# output_amp.net
KiCad netlist of a schematic drawn in EAGLE
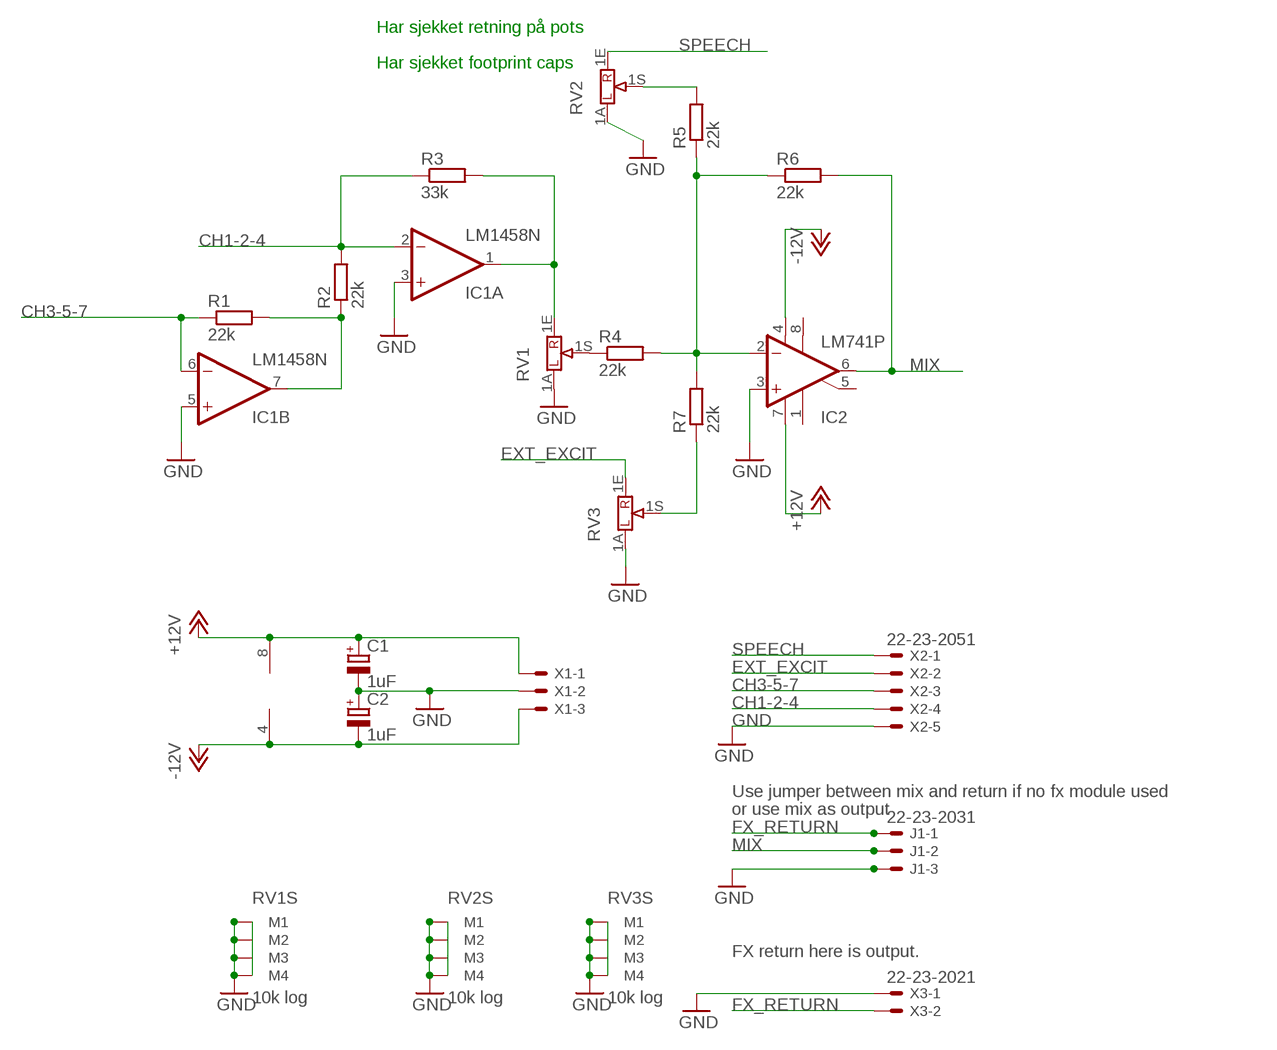
[diagram p0: schematic, sheet 1]

(export (version "E")
  (design (tool "Eeschema 10.0.6"))
  (components
    (comp (ref "C1")
      (value "1uF")
      (footprint "eagle-import:E2,5-5")
      (libsource (lib "eagle-import") (part "CPOL-EUE2.5-5"))
    )
    (comp (ref "C2")
      (value "1uF")
      (footprint "eagle-import:E2,5-5")
      (libsource (lib "eagle-import") (part "CPOL-EUE2.5-5"))
    )
    (comp (ref "IC1")
      (value "LM1458N")
      (footprint "eagle-import:DIL08")
      (libsource (lib "eagle-import") (part "1458NLM"))
    )
    (comp (ref "IC2")
      (value "LM741P")
      (footprint "eagle-import:DIL08")
      (libsource (lib "eagle-import") (part "741PLM"))
    )
    (comp (ref "J1")
      (value "22-23-2031")
      (footprint "eagle-import:22-23-2031")
      (fields (field (name "MF") "MOLEX"))
      (libsource (lib "eagle-import") (part "22-23-2031"))
    )
    (comp (ref "R1")
      (value "22k")
      (footprint "eagle-import:0207_7")
      (libsource (lib "eagle-import") (part "R-EU_0207/7"))
    )
    (comp (ref "R2")
      (value "22k")
      (footprint "eagle-import:0207_7")
      (libsource (lib "eagle-import") (part "R-EU_0207/7"))
    )
    (comp (ref "R3")
      (value "33k")
      (footprint "eagle-import:0207_7")
      (libsource (lib "eagle-import") (part "R-EU_0207/7"))
    )
    (comp (ref "R4")
      (value "22k")
      (footprint "eagle-import:0207_7")
      (libsource (lib "eagle-import") (part "R-EU_0207/7"))
    )
    (comp (ref "R5")
      (value "22k")
      (footprint "eagle-import:0207_7")
      (libsource (lib "eagle-import") (part "R-EU_0207/7"))
    )
    (comp (ref "R6")
      (value "22k")
      (footprint "eagle-import:0207_7")
      (libsource (lib "eagle-import") (part "R-EU_0207/7"))
    )
    (comp (ref "R7")
      (value "22k")
      (footprint "eagle-import:0207_7")
      (libsource (lib "eagle-import") (part "R-EU_0207/7"))
    )
    (comp (ref "RV1")
      (value "10k log")
      (footprint "eagle-import:POT16_W_BRACKET")
      (libsource (lib "eagle-import") (part "POT16_W_BRACKET{dblquote}{dblquote}"))
    )
    (comp (ref "RV2")
      (value "10k log")
      (footprint "eagle-import:POT16_W_BRACKET")
      (libsource (lib "eagle-import") (part "POT16_W_BRACKET{dblquote}{dblquote}"))
    )
    (comp (ref "RV3")
      (value "10k log")
      (footprint "eagle-import:POT16_W_BRACKET")
      (libsource (lib "eagle-import") (part "POT16_W_BRACKET{dblquote}{dblquote}"))
    )
    (comp (ref "X1")
      (value "KK-156-3")
      (footprint "eagle-import:KK-156-3")
      (libsource (lib "eagle-import") (part "KK-156-3"))
    )
    (comp (ref "X2")
      (value "22-23-2051")
      (footprint "eagle-import:22-23-2051")
      (fields (field (name "MF") "MOLEX"))
      (libsource (lib "eagle-import") (part "22-23-2051"))
    )
    (comp (ref "X3")
      (value "22-23-2021")
      (footprint "eagle-import:22-23-2021")
      (fields (field (name "MF") "MOLEX"))
      (libsource (lib "eagle-import") (part "22-23-2021"))
    )
  )
  (nets
    (net (code "1") (name "+12V") (class "Default")
      (node (ref "C1") (pin "+") (pinfunction "+_+") (pintype "passive"))
      (node (ref "IC1") (pin "8") (pinfunction "V+_8") (pintype "power_in"))
      (node (ref "IC2") (pin "7") (pinfunction "V+_7") (pintype "power_in"))
      (node (ref "X1") (pin "1") (pinfunction "S_1") (pintype "passive"))
    )
    (net (code "2") (name "-12V") (class "Default")
      (node (ref "C2") (pin "-") (pinfunction "-_-") (pintype "passive"))
      (node (ref "IC1") (pin "4") (pinfunction "V-_4") (pintype "power_in"))
      (node (ref "IC2") (pin "4") (pinfunction "V-_4") (pintype "power_in"))
      (node (ref "X1") (pin "3") (pinfunction "S_3") (pintype "passive"))
    )
    (net (code "3") (name "/CH1-2-4") (class "Default")
      (node (ref "IC1") (pin "2") (pinfunction "-IN_2") (pintype "input"))
      (node (ref "R2") (pin "2") (pinfunction "2_2") (pintype "passive"))
      (node (ref "R3") (pin "1") (pinfunction "1_1") (pintype "passive"))
      (node (ref "X2") (pin "4") (pinfunction "S_4") (pintype "passive"))
    )
    (net (code "4") (name "/CH3-5-7") (class "Default")
      (node (ref "IC1") (pin "6") (pinfunction "-IN_6") (pintype "input"))
      (node (ref "R1") (pin "1") (pinfunction "1_1") (pintype "passive"))
      (node (ref "X2") (pin "3") (pinfunction "S_3") (pintype "passive"))
    )
    (net (code "5") (name "/EXT_EXCIT") (class "Default")
      (node (ref "RV3") (pin "1E") (pinfunction "1E_1E") (pintype "passive"))
      (node (ref "X2") (pin "2") (pinfunction "S_2") (pintype "passive"))
    )
    (net (code "6") (name "/FX_RETURN") (class "Default")
      (node (ref "J1") (pin "1") (pinfunction "S_1") (pintype "passive"))
      (node (ref "X3") (pin "2") (pinfunction "S_2") (pintype "passive"))
    )
    (net (code "7") (name "/MIX") (class "Default")
      (node (ref "IC2") (pin "6") (pinfunction "OUT_6") (pintype "output"))
      (node (ref "J1") (pin "2") (pinfunction "S_2") (pintype "passive"))
      (node (ref "R6") (pin "2") (pinfunction "2_2") (pintype "passive"))
    )
    (net (code "8") (name "/SPEECH") (class "Default")
      (node (ref "RV2") (pin "1E") (pinfunction "1E_1E") (pintype "passive"))
      (node (ref "X2") (pin "1") (pinfunction "S_1") (pintype "passive"))
    )
    (net (code "9") (name "GND") (class "Default")
      (node (ref "C1") (pin "-") (pinfunction "-_-") (pintype "passive"))
      (node (ref "C2") (pin "+") (pinfunction "+_+") (pintype "passive"))
      (node (ref "IC1") (pin "3") (pinfunction "+IN_3") (pintype "input"))
      (node (ref "IC1") (pin "5") (pinfunction "+IN_5") (pintype "input"))
      (node (ref "IC2") (pin "3") (pinfunction "+IN_3") (pintype "input"))
      (node (ref "J1") (pin "3") (pinfunction "S_3") (pintype "passive"))
      (node (ref "RV1") (pin "1A") (pinfunction "1A_1A") (pintype "passive"))
      (node (ref "RV1") (pin "M1") (pinfunction "M1_M1") (pintype "passive"))
      (node (ref "RV1") (pin "M2") (pinfunction "M2_M2") (pintype "passive"))
      (node (ref "RV1") (pin "M3") (pinfunction "M3_M3") (pintype "passive"))
      (node (ref "RV1") (pin "M4") (pinfunction "M4_M4") (pintype "passive"))
      (node (ref "RV2") (pin "1A") (pinfunction "1A_1A") (pintype "passive"))
      (node (ref "RV2") (pin "M1") (pinfunction "M1_M1") (pintype "passive"))
      (node (ref "RV2") (pin "M2") (pinfunction "M2_M2") (pintype "passive"))
      (node (ref "RV2") (pin "M3") (pinfunction "M3_M3") (pintype "passive"))
      (node (ref "RV2") (pin "M4") (pinfunction "M4_M4") (pintype "passive"))
      (node (ref "RV3") (pin "1A") (pinfunction "1A_1A") (pintype "passive"))
      (node (ref "RV3") (pin "M1") (pinfunction "M1_M1") (pintype "passive"))
      (node (ref "RV3") (pin "M2") (pinfunction "M2_M2") (pintype "passive"))
      (node (ref "RV3") (pin "M3") (pinfunction "M3_M3") (pintype "passive"))
      (node (ref "RV3") (pin "M4") (pinfunction "M4_M4") (pintype "passive"))
      (node (ref "X1") (pin "2") (pinfunction "S_2") (pintype "passive"))
      (node (ref "X2") (pin "5") (pinfunction "S_5") (pintype "passive"))
      (node (ref "X3") (pin "1") (pinfunction "S_1") (pintype "passive"))
    )
    (net (code "10") (name "Net-(IC1A-OUT)") (class "Default")
      (node (ref "IC1") (pin "1") (pinfunction "OUT_1") (pintype "output"))
      (node (ref "R3") (pin "2") (pinfunction "2_2") (pintype "passive"))
      (node (ref "RV1") (pin "1E") (pinfunction "1E_1E") (pintype "passive"))
    )
    (net (code "11") (name "Net-(IC1B-OUT)") (class "Default")
      (node (ref "IC1") (pin "7") (pinfunction "OUT_7") (pintype "output"))
      (node (ref "R1") (pin "2") (pinfunction "2_2") (pintype "passive"))
      (node (ref "R2") (pin "1") (pinfunction "1_1") (pintype "passive"))
    )
    (net (code "12") (name "Net-(IC2--IN)") (class "Default")
      (node (ref "IC2") (pin "2") (pinfunction "-IN_2") (pintype "input"))
      (node (ref "R4") (pin "2") (pinfunction "2_2") (pintype "passive"))
      (node (ref "R5") (pin "1") (pinfunction "1_1") (pintype "passive"))
      (node (ref "R6") (pin "1") (pinfunction "1_1") (pintype "passive"))
      (node (ref "R7") (pin "2") (pinfunction "2_2") (pintype "passive"))
    )
    (net (code "13") (name "Net-(R4-Pad1)") (class "Default")
      (node (ref "R4") (pin "1") (pinfunction "1_1") (pintype "passive"))
      (node (ref "RV1") (pin "1S") (pinfunction "1S_1S") (pintype "passive"))
    )
    (net (code "14") (name "Net-(R5-Pad2)") (class "Default")
      (node (ref "R5") (pin "2") (pinfunction "2_2") (pintype "passive"))
      (node (ref "RV2") (pin "1S") (pinfunction "1S_1S") (pintype "passive"))
    )
    (net (code "15") (name "Net-(R7-Pad1)") (class "Default")
      (node (ref "R7") (pin "1") (pinfunction "1_1") (pintype "passive"))
      (node (ref "RV3") (pin "1S") (pinfunction "1S_1S") (pintype "passive"))
    )
    (net (code "16") (name "unconnected-(IC2-ON1-Pad1)") (class "Default")
      (node (ref "IC2") (pin "1") (pinfunction "ON1_1") (pintype "passive"))
    )
    (net (code "17") (name "unconnected-(IC2-ON2-Pad5)") (class "Default")
      (node (ref "IC2") (pin "5") (pinfunction "ON2_5") (pintype "passive"))
    )
    (net (code "18") (name "unconnected-(IC2-OPT-Pad8)") (class "Default")
      (node (ref "IC2") (pin "8") (pinfunction "OPT_8") (pintype "passive"))
    )
  )
)
